# BUS_Board.net
KiCad netlist of a schematic drawn in Altium Designer
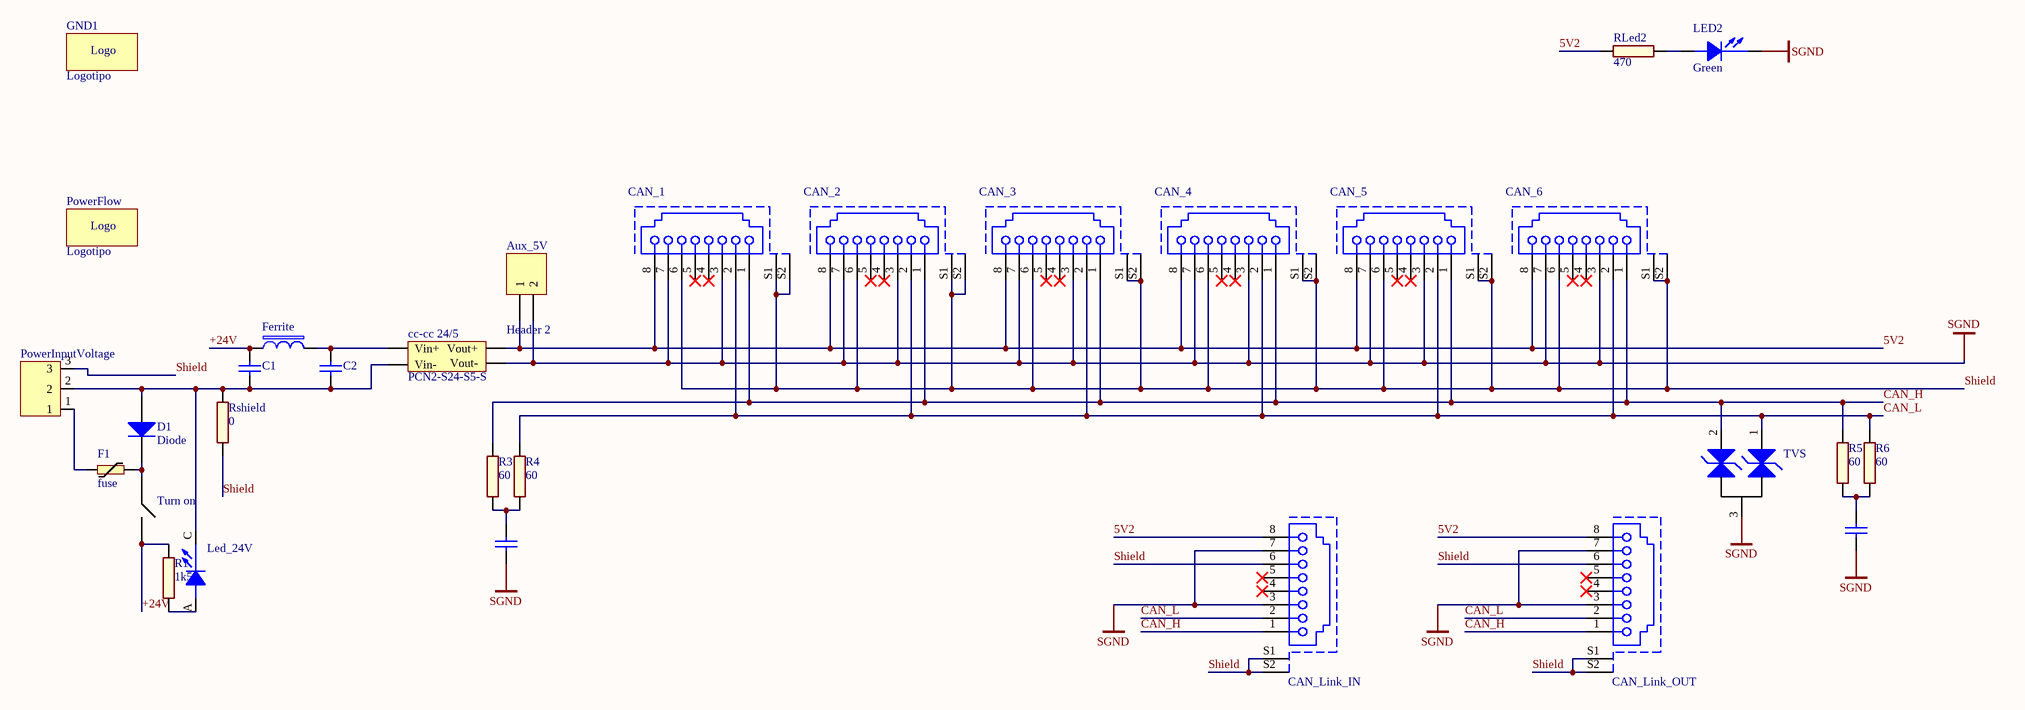
[diagram p0: BUS_Board.SchDoc]

(export (version "E")
  (design (tool "Eeschema 10.0.6"))
  (components
    (comp (ref "Aux_5V")
      (value "Header 2")
      (footprint "HDR1X2")
      (description "Header, 2-Pin")
      (fields (field (name "PUBLISHER") "Altium Limited"))
      (libsource (lib "Miscellaneous Connectors") (part "Header 2"))
    )
    (comp (ref "C1")
      (value "Capacitor")
      (footprint "CAPC_1206")
      (fields (field (name "VOLTAGE") "50 V"))
      (libsource (lib "myLibraryAltium") (part "Capacitor"))
    )
    (comp (ref "C2")
      (value "Capacitor")
      (footprint "CAPC_1206")
      (fields (field (name "VOLTAGE") "50 V"))
      (libsource (lib "myLibraryAltium") (part "Capacitor"))
    )
    (comp (ref "CAN_1")
      (value "61500814221")
      (footprint "61500814221")
      (description "Modular Jack Horizontal Shielded 8P8C Tab Down WR-MJ")
      (fields (field (name "PUBLISHER") "Wurth Elektronik"))
      (libsource (lib "Modular Jack Connector_WR-MJ") (part "61500814221"))
    )
    (comp (ref "CAN_2")
      (value "61500814221")
      (footprint "61500814221")
      (description "Modular Jack Horizontal Shielded 8P8C Tab Down WR-MJ")
      (fields (field (name "PUBLISHER") "Wurth Elektronik"))
      (libsource (lib "Modular Jack Connector_WR-MJ") (part "61500814221"))
    )
    (comp (ref "CAN_3")
      (value "61500814221")
      (footprint "61500814221")
      (description "Modular Jack Horizontal Shielded 8P8C Tab Down WR-MJ")
      (fields (field (name "PUBLISHER") "Wurth Elektronik"))
      (libsource (lib "Modular Jack Connector_WR-MJ") (part "61500814221"))
    )
    (comp (ref "CAN_4")
      (value "61500814221")
      (footprint "61500814221")
      (description "Modular Jack Horizontal Shielded 8P8C Tab Down WR-MJ")
      (fields (field (name "PUBLISHER") "Wurth Elektronik"))
      (libsource (lib "Modular Jack Connector_WR-MJ") (part "61500814221"))
    )
    (comp (ref "CAN_5")
      (value "61500814221")
      (footprint "61500814221")
      (description "Modular Jack Horizontal Shielded 8P8C Tab Down WR-MJ")
      (fields (field (name "PUBLISHER") "Wurth Elektronik"))
      (libsource (lib "Modular Jack Connector_WR-MJ") (part "61500814221"))
    )
    (comp (ref "CAN_6")
      (value "61500814221")
      (footprint "61500814221")
      (description "Modular Jack Horizontal Shielded 8P8C Tab Down WR-MJ")
      (fields (field (name "PUBLISHER") "Wurth Elektronik"))
      (libsource (lib "Modular Jack Connector_WR-MJ") (part "61500814221"))
    )
    (comp (ref "CAN_Link_IN")
      (value "61500814221")
      (footprint "61500814221")
      (description "Modular Jack Horizontal Shielded 8P8C Tab Down WR-MJ")
      (fields (field (name "PUBLISHER") "Wurth Elektronik"))
      (libsource (lib "Modular Jack Connector_WR-MJ") (part "61500814221"))
    )
    (comp (ref "CAN_Link_OUT")
      (value "61500814221")
      (footprint "61500814221")
      (description "Modular Jack Horizontal Shielded 8P8C Tab Down WR-MJ")
      (fields (field (name "PUBLISHER") "Wurth Elektronik"))
      (libsource (lib "Modular Jack Connector_WR-MJ") (part "61500814221"))
    )
    (comp (ref "cc-cc 24/5")
      (value "PCN2-S24-S5-S")
      (footprint "PCN2-S")
      (libsource (lib "myLibraryAltium") (part "PCN2-S24-S5-S"))
    )
    (comp (ref "CL")
      (value "Capacitor")
      (footprint "CAPC_0805")
      (libsource (lib "myLibraryAltium") (part "Capacitor"))
    )
    (comp (ref "CL2")
      (value "Capacitor")
      (footprint "CAPC_0805")
      (libsource (lib "myLibraryAltium") (part "Capacitor"))
    )
    (comp (ref "D1")
      (value "Diode")
      (footprint "Diode_SOD-123")
      (libsource (lib "myLibraryAltium") (part "Diode"))
    )
    (comp (ref "F1") (value "fuse") (footprint "fuse_1206") (libsource (lib "myLibraryAltium") (part "fuse")))
    (comp (ref "Ferrite")
      (value "Ferrite Bead")
      (footprint "FERR_0805")
      (libsource (lib "myLibraryAltium") (part "Ferrite Bead"))
    )
    (comp (ref "GND1")
      (value "Logotipo")
      (footprint "Dangerous_Logo")
      (libsource (lib "myLibraryAltium") (part "Logotipo"))
    )
    (comp (ref "LED2")
      (value "Green")
      (footprint "CD2012-0805")
      (description "LED 2X1.2MM 570NM GN WTR CLR SMD")
      (fields (field (name "MANUFACTURER") "Kingbright") (field (name "MPN") "APT2012CGCK"))
      (libsource (lib "myLibraryAltium") (part "LED_GREEN"))
    )
    (comp (ref "Led_24V")
      (value "Green")
      (footprint "CD2012-0805")
      (description "LED 2X1.2MM 570NM GN WTR CLR SMD")
      (fields (field (name "MANUFACTURER") "Kingbright") (field (name "MPN") "APT2012CGCK"))
      (libsource (lib "") (part "LED_GREEN_1"))
    )
    (comp (ref "PowerFlow")
      (value "Logotipo")
      (footprint "PowerFlow_LOGO")
      (libsource (lib "myLibraryAltium") (part "Logotipo"))
    )
    (comp (ref "PowerInputVoltage")
      (value "con-phoenix-3")
      (footprint "MCV3-LOCK")
      (libsource (lib "myLibraryAltium") (part "con-phoenix-3"))
    )
    (comp (ref "R1")
      (value "1k5")
      (footprint "RESC_0805")
      (description "Thick film resistor, SMD 0402, 1/16W, 1%")
      (fields (field (name "MANUFACTURER") "Generic"))
      (libsource (lib "myLibraryAltium") (part "R2"))
    )
    (comp (ref "R3")
      (value "60")
      (footprint "RESC_0805")
      (description "Thick film resistor, SMD 0402, 1/16W, 1%")
      (fields (field (name "MANUFACTURER") "Generic"))
      (libsource (lib "myLibraryAltium") (part "R2"))
    )
    (comp (ref "R4")
      (value "60")
      (footprint "RESC_0805")
      (description "Thick film resistor, SMD 0402, 1/16W, 1%")
      (fields (field (name "MANUFACTURER") "Generic"))
      (libsource (lib "myLibraryAltium") (part "R2"))
    )
    (comp (ref "R5")
      (value "60")
      (footprint "RESC_0805")
      (description "Thick film resistor, SMD 0402, 1/16W, 1%")
      (fields (field (name "MANUFACTURER") "Generic"))
      (libsource (lib "myLibraryAltium") (part "R2"))
    )
    (comp (ref "R6")
      (value "60")
      (footprint "RESC_0805")
      (description "Thick film resistor, SMD 0402, 1/16W, 1%")
      (fields (field (name "MANUFACTURER") "Generic"))
      (libsource (lib "myLibraryAltium") (part "R2"))
    )
    (comp (ref "RLed2")
      (value "470")
      (footprint "RESC_0805")
      (description "Thick film resistor, SMD 0402, 1/16W, 1%")
      (fields (field (name "MANUFACTURER") "Generic"))
      (libsource (lib "") (part "R2_1"))
    )
    (comp (ref "Rshield")
      (value "0")
      (footprint "RESC_0805")
      (description "Thick film resistor, SMD 0402, 1/16W, 1%")
      (fields (field (name "MANUFACTURER") "Generic"))
      (libsource (lib "myLibraryAltium") (part "R2"))
    )
    (comp (ref "Turn on")
      (value "switch_single")
      (footprint "SW-1-A11J")
      (libsource (lib "myLibraryAltium") (part "switch_single"))
    )
    (comp (ref "TVS")
      (value "Diode_TVS_Array")
      (footprint "SOT23-3")
      (libsource (lib "myLibraryAltium") (part "Diode_TVS_Array"))
    )
  )
  (nets
    (net (code "1") (name "/+24V") (class "Default")
      (node (ref "C1") (pin "2") (pinfunction "2_2") (pintype "passive"))
      (node (ref "Ferrite") (pin "1") (pinfunction "1_1") (pintype "passive"))
      (node (ref "R1") (pin "2") (pinfunction "2_2") (pintype "passive"))
      (node (ref "Turn on") (pin "2") (pinfunction "2_2") (pintype "passive"))
    )
    (net (code "2") (name "/5V2") (class "Default")
      (node (ref "Aux_5V") (pin "1") (pinfunction "1_1") (pintype "passive"))
      (node (ref "CAN_1") (pin "8") (pinfunction "8_8") (pintype "passive"))
      (node (ref "CAN_2") (pin "8") (pinfunction "8_8") (pintype "passive"))
      (node (ref "CAN_3") (pin "8") (pinfunction "8_8") (pintype "passive"))
      (node (ref "CAN_4") (pin "8") (pinfunction "8_8") (pintype "passive"))
      (node (ref "CAN_5") (pin "8") (pinfunction "8_8") (pintype "passive"))
      (node (ref "CAN_6") (pin "8") (pinfunction "8_8") (pintype "passive"))
      (node (ref "CAN_Link_IN") (pin "8") (pinfunction "8_8") (pintype "passive"))
      (node (ref "CAN_Link_OUT") (pin "8") (pinfunction "8_8") (pintype "passive"))
      (node (ref "RLed2") (pin "1") (pinfunction "1_1") (pintype "passive"))
      (node (ref "cc-cc 24/5") (pin "6") (pinfunction "Vout+_6") (pintype "passive"))
    )
    (net (code "3") (name "/CAN_H") (class "Default")
      (node (ref "CAN_1") (pin "1") (pinfunction "1_1") (pintype "passive"))
      (node (ref "CAN_2") (pin "1") (pinfunction "1_1") (pintype "passive"))
      (node (ref "CAN_3") (pin "1") (pinfunction "1_1") (pintype "passive"))
      (node (ref "CAN_4") (pin "1") (pinfunction "1_1") (pintype "passive"))
      (node (ref "CAN_5") (pin "1") (pinfunction "1_1") (pintype "passive"))
      (node (ref "CAN_6") (pin "1") (pinfunction "1_1") (pintype "passive"))
      (node (ref "CAN_Link_IN") (pin "1") (pinfunction "1_1") (pintype "passive"))
      (node (ref "CAN_Link_OUT") (pin "1") (pinfunction "1_1") (pintype "passive"))
      (node (ref "R3") (pin "2") (pinfunction "2_2") (pintype "passive"))
      (node (ref "R5") (pin "2") (pinfunction "2_2") (pintype "passive"))
      (node (ref "TVS") (pin "2") (pinfunction "2_2") (pintype "passive"))
    )
    (net (code "4") (name "/CAN_L") (class "Default")
      (node (ref "CAN_1") (pin "2") (pinfunction "2_2") (pintype "passive"))
      (node (ref "CAN_2") (pin "2") (pinfunction "2_2") (pintype "passive"))
      (node (ref "CAN_3") (pin "2") (pinfunction "2_2") (pintype "passive"))
      (node (ref "CAN_4") (pin "2") (pinfunction "2_2") (pintype "passive"))
      (node (ref "CAN_5") (pin "2") (pinfunction "2_2") (pintype "passive"))
      (node (ref "CAN_6") (pin "2") (pinfunction "2_2") (pintype "passive"))
      (node (ref "CAN_Link_IN") (pin "2") (pinfunction "2_2") (pintype "passive"))
      (node (ref "CAN_Link_OUT") (pin "2") (pinfunction "2_2") (pintype "passive"))
      (node (ref "R4") (pin "2") (pinfunction "2_2") (pintype "passive"))
      (node (ref "R6") (pin "2") (pinfunction "2_2") (pintype "passive"))
      (node (ref "TVS") (pin "1") (pinfunction "1_1") (pintype "passive"))
    )
    (net (code "5") (name "/Shield") (class "Default")
      (node (ref "CAN_1") (pin "6") (pinfunction "6_6") (pintype "passive"))
      (node (ref "CAN_1") (pin "S1") (pinfunction "Shield_S1") (pintype "passive"))
      (node (ref "CAN_1") (pin "S2") (pinfunction "Shield_S2") (pintype "passive"))
      (node (ref "CAN_2") (pin "6") (pinfunction "6_6") (pintype "passive"))
      (node (ref "CAN_2") (pin "S1") (pinfunction "Shield_S1") (pintype "passive"))
      (node (ref "CAN_2") (pin "S2") (pinfunction "Shield_S2") (pintype "passive"))
      (node (ref "CAN_3") (pin "6") (pinfunction "6_6") (pintype "passive"))
      (node (ref "CAN_3") (pin "S1") (pinfunction "Shield_S1") (pintype "passive"))
      (node (ref "CAN_3") (pin "S2") (pinfunction "Shield_S2") (pintype "passive"))
      (node (ref "CAN_4") (pin "6") (pinfunction "6_6") (pintype "passive"))
      (node (ref "CAN_4") (pin "S1") (pinfunction "Shield_S1") (pintype "passive"))
      (node (ref "CAN_4") (pin "S2") (pinfunction "Shield_S2") (pintype "passive"))
      (node (ref "CAN_5") (pin "6") (pinfunction "6_6") (pintype "passive"))
      (node (ref "CAN_5") (pin "S1") (pinfunction "Shield_S1") (pintype "passive"))
      (node (ref "CAN_5") (pin "S2") (pinfunction "Shield_S2") (pintype "passive"))
      (node (ref "CAN_6") (pin "6") (pinfunction "6_6") (pintype "passive"))
      (node (ref "CAN_6") (pin "S1") (pinfunction "Shield_S1") (pintype "passive"))
      (node (ref "CAN_6") (pin "S2") (pinfunction "Shield_S2") (pintype "passive"))
      (node (ref "CAN_Link_IN") (pin "6") (pinfunction "6_6") (pintype "passive"))
      (node (ref "CAN_Link_IN") (pin "S1") (pinfunction "Shield_S1") (pintype "passive"))
      (node (ref "CAN_Link_IN") (pin "S2") (pinfunction "Shield_S2") (pintype "passive"))
      (node (ref "CAN_Link_OUT") (pin "6") (pinfunction "6_6") (pintype "passive"))
      (node (ref "CAN_Link_OUT") (pin "S1") (pinfunction "Shield_S1") (pintype "passive"))
      (node (ref "CAN_Link_OUT") (pin "S2") (pinfunction "Shield_S2") (pintype "passive"))
      (node (ref "PowerInputVoltage") (pin "3") (pinfunction "3_3") (pintype "passive"))
      (node (ref "Rshield") (pin "1") (pinfunction "1_1") (pintype "passive"))
    )
    (net (code "6") (name "Net-(CL-Pad1)") (class "Default")
      (node (ref "CL") (pin "1") (pinfunction "1_1") (pintype "passive"))
      (node (ref "R3") (pin "1") (pinfunction "1_1") (pintype "passive"))
      (node (ref "R4") (pin "1") (pinfunction "1_1") (pintype "passive"))
    )
    (net (code "7") (name "Net-(CL2-Pad1)") (class "Default")
      (node (ref "CL2") (pin "1") (pinfunction "1_1") (pintype "passive"))
      (node (ref "R5") (pin "1") (pinfunction "1_1") (pintype "passive"))
      (node (ref "R6") (pin "1") (pinfunction "1_1") (pintype "passive"))
    )
    (net (code "8") (name "Net-(D1-A)") (class "Default")
      (node (ref "C1") (pin "1") (pinfunction "1_1") (pintype "passive"))
      (node (ref "C2") (pin "1") (pinfunction "1_1") (pintype "passive"))
      (node (ref "D1") (pin "1") (pinfunction "A_1") (pintype "passive"))
      (node (ref "Led_24V") (pin "C") (pinfunction "CATHODE_C") (pintype "passive"))
      (node (ref "PowerInputVoltage") (pin "2") (pinfunction "2_2") (pintype "passive"))
      (node (ref "Rshield") (pin "2") (pinfunction "2_2") (pintype "passive"))
      (node (ref "cc-cc 24/5") (pin "2") (pinfunction "Vin-_2") (pintype "passive"))
    )
    (net (code "9") (name "Net-(D1-K)") (class "Default")
      (node (ref "D1") (pin "2") (pinfunction "K_2") (pintype "passive"))
      (node (ref "F1") (pin "1") (pinfunction "1_1") (pintype "passive"))
      (node (ref "Turn on") (pin "1") (pinfunction "1_1") (pintype "passive"))
    )
    (net (code "10") (name "Net-(F1-Pad2)") (class "Default")
      (node (ref "F1") (pin "2") (pinfunction "2_2") (pintype "passive"))
      (node (ref "PowerInputVoltage") (pin "1") (pinfunction "1_1") (pintype "passive"))
    )
    (net (code "11") (name "Net-(LED2-ANODE)") (class "Default")
      (node (ref "LED2") (pin "A") (pinfunction "ANODE_A") (pintype "passive"))
      (node (ref "RLed2") (pin "2") (pinfunction "2_2") (pintype "passive"))
    )
    (net (code "12") (name "Net-(Led_24V-ANODE)") (class "Default")
      (node (ref "Led_24V") (pin "A") (pinfunction "ANODE_A") (pintype "passive"))
      (node (ref "R1") (pin "1") (pinfunction "1_1") (pintype "passive"))
    )
    (net (code "13") (name "Net-(cc-cc 24/5-Vin+)") (class "Default")
      (node (ref "C2") (pin "2") (pinfunction "2_2") (pintype "passive"))
      (node (ref "Ferrite") (pin "2") (pinfunction "2_2") (pintype "passive"))
      (node (ref "cc-cc 24/5") (pin "1") (pinfunction "Vin+_1") (pintype "passive"))
    )
    (net (code "14") (name "SGND") (class "Default")
      (node (ref "Aux_5V") (pin "2") (pinfunction "2_2") (pintype "passive"))
      (node (ref "CAN_1") (pin "3") (pinfunction "3_3") (pintype "passive"))
      (node (ref "CAN_1") (pin "7") (pinfunction "7_7") (pintype "passive"))
      (node (ref "CAN_2") (pin "3") (pinfunction "3_3") (pintype "passive"))
      (node (ref "CAN_2") (pin "7") (pinfunction "7_7") (pintype "passive"))
      (node (ref "CAN_3") (pin "3") (pinfunction "3_3") (pintype "passive"))
      (node (ref "CAN_3") (pin "7") (pinfunction "7_7") (pintype "passive"))
      (node (ref "CAN_4") (pin "3") (pinfunction "3_3") (pintype "passive"))
      (node (ref "CAN_4") (pin "7") (pinfunction "7_7") (pintype "passive"))
      (node (ref "CAN_5") (pin "3") (pinfunction "3_3") (pintype "passive"))
      (node (ref "CAN_5") (pin "7") (pinfunction "7_7") (pintype "passive"))
      (node (ref "CAN_6") (pin "3") (pinfunction "3_3") (pintype "passive"))
      (node (ref "CAN_6") (pin "7") (pinfunction "7_7") (pintype "passive"))
      (node (ref "CAN_Link_IN") (pin "3") (pinfunction "3_3") (pintype "passive"))
      (node (ref "CAN_Link_IN") (pin "7") (pinfunction "7_7") (pintype "passive"))
      (node (ref "CAN_Link_OUT") (pin "3") (pinfunction "3_3") (pintype "passive"))
      (node (ref "CAN_Link_OUT") (pin "7") (pinfunction "7_7") (pintype "passive"))
      (node (ref "CL") (pin "2") (pinfunction "2_2") (pintype "passive"))
      (node (ref "CL2") (pin "2") (pinfunction "2_2") (pintype "passive"))
      (node (ref "LED2") (pin "C") (pinfunction "CATHODE_C") (pintype "passive"))
      (node (ref "TVS") (pin "3") (pinfunction "3_3") (pintype "passive"))
      (node (ref "cc-cc 24/5") (pin "4") (pinfunction "Vout-_4") (pintype "passive"))
    )
    (net (code "15") (name "unconnected-(CAN_1-Pad4)") (class "Default")
      (node (ref "CAN_1") (pin "4") (pinfunction "4_4") (pintype "passive+no_connect"))
    )
    (net (code "16") (name "unconnected-(CAN_1-Pad5)") (class "Default")
      (node (ref "CAN_1") (pin "5") (pinfunction "5_5") (pintype "passive+no_connect"))
    )
    (net (code "17") (name "unconnected-(CAN_2-Pad4)") (class "Default")
      (node (ref "CAN_2") (pin "4") (pinfunction "4_4") (pintype "passive+no_connect"))
    )
    (net (code "18") (name "unconnected-(CAN_2-Pad5)") (class "Default")
      (node (ref "CAN_2") (pin "5") (pinfunction "5_5") (pintype "passive+no_connect"))
    )
    (net (code "19") (name "unconnected-(CAN_3-Pad4)") (class "Default")
      (node (ref "CAN_3") (pin "4") (pinfunction "4_4") (pintype "passive+no_connect"))
    )
    (net (code "20") (name "unconnected-(CAN_3-Pad5)") (class "Default")
      (node (ref "CAN_3") (pin "5") (pinfunction "5_5") (pintype "passive+no_connect"))
    )
    (net (code "21") (name "unconnected-(CAN_4-Pad4)") (class "Default")
      (node (ref "CAN_4") (pin "4") (pinfunction "4_4") (pintype "passive+no_connect"))
    )
    (net (code "22") (name "unconnected-(CAN_4-Pad5)") (class "Default")
      (node (ref "CAN_4") (pin "5") (pinfunction "5_5") (pintype "passive+no_connect"))
    )
    (net (code "23") (name "unconnected-(CAN_5-Pad4)") (class "Default")
      (node (ref "CAN_5") (pin "4") (pinfunction "4_4") (pintype "passive+no_connect"))
    )
    (net (code "24") (name "unconnected-(CAN_5-Pad5)") (class "Default")
      (node (ref "CAN_5") (pin "5") (pinfunction "5_5") (pintype "passive+no_connect"))
    )
    (net (code "25") (name "unconnected-(CAN_6-Pad4)") (class "Default")
      (node (ref "CAN_6") (pin "4") (pinfunction "4_4") (pintype "passive+no_connect"))
    )
    (net (code "26") (name "unconnected-(CAN_6-Pad5)") (class "Default")
      (node (ref "CAN_6") (pin "5") (pinfunction "5_5") (pintype "passive+no_connect"))
    )
    (net (code "27") (name "unconnected-(CAN_Link_IN-Pad4)") (class "Default")
      (node (ref "CAN_Link_IN") (pin "4") (pinfunction "4_4") (pintype "passive+no_connect"))
    )
    (net (code "28") (name "unconnected-(CAN_Link_IN-Pad5)") (class "Default")
      (node (ref "CAN_Link_IN") (pin "5") (pinfunction "5_5") (pintype "passive+no_connect"))
    )
    (net (code "29") (name "unconnected-(CAN_Link_OUT-Pad4)") (class "Default")
      (node (ref "CAN_Link_OUT") (pin "4") (pinfunction "4_4") (pintype "passive+no_connect"))
    )
    (net (code "30") (name "unconnected-(CAN_Link_OUT-Pad5)") (class "Default")
      (node (ref "CAN_Link_OUT") (pin "5") (pinfunction "5_5") (pintype "passive+no_connect"))
    )
  )
)
